# Sheet1.net
KiCad netlist of a schematic drawn in Altium Designer
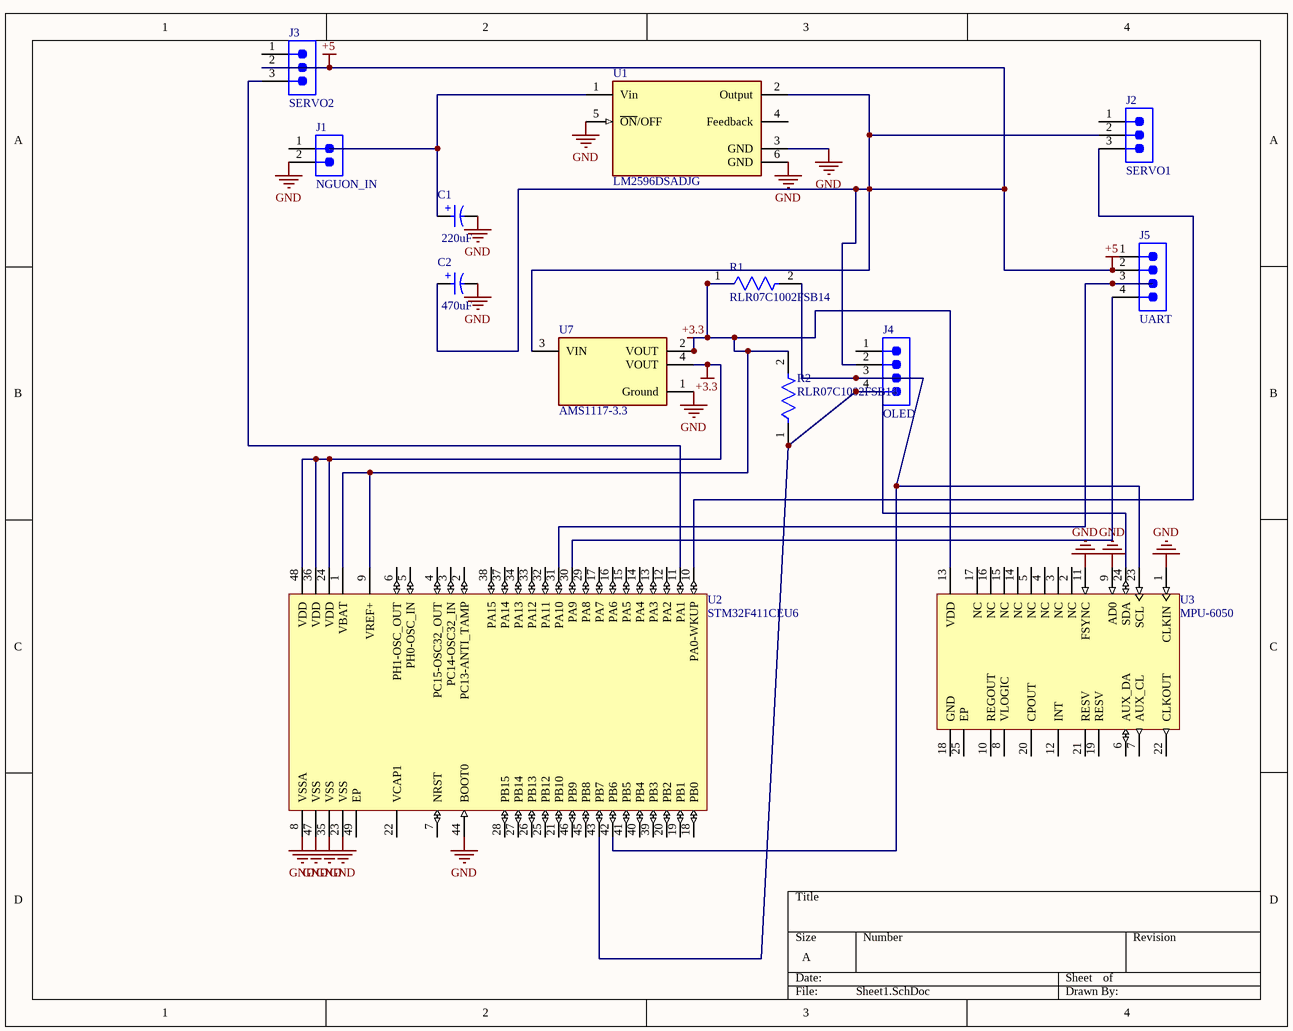
[diagram p0: Sheet1.SchDoc]

(export (version "E")
  (design (tool "Eeschema 10.0.6"))
  (components
    (comp (ref "C1")
      (value "220uF")
      (footprint "WCAP-PTHR_D8H11.5")
      (description "WCAP-PTHR Aluminum Polymer Capacitors")
      (fields (field (name "TOLERANCE") "20%"))
      (libsource (lib "Altium Content Vault") (part "Capacitor_Polarized"))
    )
    (comp (ref "C2")
      (value "470uF")
      (footprint "WCAP-PTHR_D8H11.5")
      (description "WCAP-PTHR Aluminum Polymer Capacitors")
      (fields (field (name "TOLERANCE") "20%"))
      (libsource (lib "Altium Content Vault") (part "Capacitor_Polarized"))
    )
    (comp (ref "J1")
      (value "NGUON_IN")
      (footprint "61300211121")
      (description "THT Vertical Pin Header WR-PHD, Pitch 2.54 mm, Single Row, 2 pins")
      (libsource (lib "Altium Content Vault") (part "Header_Male_1R_02P"))
    )
    (comp (ref "J2")
      (value "SERVO1")
      (footprint "61300311121")
      (description "THT Vertical Pin Header WR-PHD, Pitch 2.54 mm, Single Row, 3 pins")
      (libsource (lib "Altium Content Vault") (part "Header_Male_1R_03P"))
    )
    (comp (ref "J3")
      (value "SERVO2")
      (footprint "61300311121")
      (description "THT Vertical Pin Header WR-PHD, Pitch 2.54 mm, Single Row, 3 pins")
      (libsource (lib "Altium Content Vault") (part "Header_Male_1R_03P"))
    )
    (comp (ref "J4")
      (value "OLED")
      (footprint "61300411121")
      (description "THT Vertical Pin Header WR-PHD, Pitch 2.54 mm, Single Row, 4 pins")
      (libsource (lib "Altium Content Vault") (part "Header_Male_1R_04P"))
    )
    (comp (ref "J5")
      (value "UART")
      (footprint "61300411121")
      (description "THT Vertical Pin Header WR-PHD, Pitch 2.54 mm, Single Row, 4 pins")
      (libsource (lib "Altium Content Vault") (part "Header_Male_1R_04P"))
    )
    (comp (ref "R1")
      (value "RLR07C1002FSB14")
      (footprint "FP-RLR07-MFG")
      (fields (field (name "TOLERANCE") "1%"))
      (libsource (lib "Altium Content Vault") (part "1029c3af85768c4190bb7ad29bc67b5"))
    )
    (comp (ref "R2")
      (value "RLR07C1002FSB14")
      (footprint "FP-RLR07-MFG")
      (fields (field (name "TOLERANCE") "1%"))
      (libsource (lib "Altium Content Vault") (part "1029c3af85768c4190bb7ad29bc67b5"))
    )
    (comp (ref "U1")
      (value "LM2596DSADJG")
      (footprint "FP-936A-02-MFG")
      (description "IC REG MULT CONFG ADJ 3A D2PAK-5")
      (fields
        (field (name "OCTOPART") "https://octopart.com/lm2596dsadjg-on+semiconductor-12437034")
        (field (name "MANUFACTURER") "ON Semiconductor")
      )
      (libsource (lib "Altium Content Vault") (part "6e009c68f80b765d55aa2e30e527964"))
    )
    (comp (ref "U2")
      (value "STM32F411CEU6")
      (footprint "STM-UFQFPN48_L")
      (libsource (lib "Altium Content Vault") (part "MC-ARM-STM32F411-UFQFPN48"))
    )
    (comp (ref "U3")
      (value "MPU-6050")
      (footprint "IS-QFN-24_V")
      (fields (field (name "MANUFACTURER") "InvenSense"))
      (libsource (lib "Altium Content Vault") (part "IS-MPU-6050-QFN-24"))
    )
    (comp (ref "U7")
      (value "AMS1117-3.3")
      (footprint "FP-AMS1117-IPC_C")
      (description "LDO Voltage Regulators 1A, 3.3V")
      (fields
        (field (name "OCTOPART") "https://octopart.com/ams1117-3.3-advanced+monolithic+systems-25899300")
        (field (name "MANUFACTURER") "Advanced Monolithic Systems")
      )
      (libsource (lib "Altium Content Vault") (part "8bdbb5f8e77002000e30dd2845d0354"))
    )
  )
  (nets
    (net (code "1") (name "+3.3") (class "Default")
      (node (ref "R1") (pin "1") (pinfunction "1_1") (pintype "passive"))
      (node (ref "R2") (pin "2") (pinfunction "2_2") (pintype "passive"))
      (node (ref "U2") (pin "1") (pinfunction "VBAT_1") (pintype "power_in"))
      (node (ref "U2") (pin "24") (pinfunction "VDD_24") (pintype "power_in"))
      (node (ref "U2") (pin "36") (pinfunction "VDD_36") (pintype "power_in"))
      (node (ref "U2") (pin "48") (pinfunction "VDD_48") (pintype "power_in"))
      (node (ref "U2") (pin "9") (pinfunction "VREF+_9") (pintype "power_in"))
      (node (ref "U3") (pin "13") (pinfunction "VDD_13") (pintype "power_in"))
      (node (ref "U7") (pin "2") (pinfunction "VOUT_2") (pintype "passive"))
      (node (ref "U7") (pin "4") (pinfunction "VOUT_4") (pintype "passive"))
    )
    (net (code "2") (name "+5") (class "Default")
      (node (ref "C2") (pin "1") (pinfunction "P_1") (pintype "passive"))
      (node (ref "J2") (pin "2") (pinfunction "2_2") (pintype "passive"))
      (node (ref "J3") (pin "2") (pinfunction "2_2") (pintype "passive"))
      (node (ref "J4") (pin "2") (pinfunction "2_2") (pintype "passive"))
      (node (ref "J5") (pin "2") (pinfunction "2_2") (pintype "passive"))
      (node (ref "U1") (pin "2") (pinfunction "Output_2") (pintype "power_in"))
      (node (ref "U7") (pin "3") (pinfunction "VIN_3") (pintype "power_in"))
    )
    (net (code "3") (name "GND") (class "Default")
      (node (ref "C1") (pin "2") (pinfunction "N_2") (pintype "passive"))
      (node (ref "C2") (pin "2") (pinfunction "N_2") (pintype "passive"))
      (node (ref "J1") (pin "2") (pinfunction "2_2") (pintype "passive"))
      (node (ref "U1") (pin "3") (pinfunction "GND_3") (pintype "power_in"))
      (node (ref "U1") (pin "5") (pinfunction "~{ON}/OFF_5") (pintype "input"))
      (node (ref "U1") (pin "6") (pinfunction "GND_6") (pintype "power_in"))
      (node (ref "U2") (pin "23") (pinfunction "VSS_23") (pintype "power_in"))
      (node (ref "U2") (pin "35") (pinfunction "VSS_35") (pintype "power_in"))
      (node (ref "U2") (pin "44") (pinfunction "BOOT0_44") (pintype "input"))
      (node (ref "U2") (pin "47") (pinfunction "VSS_47") (pintype "power_in"))
      (node (ref "U2") (pin "8") (pinfunction "VSSA_8") (pintype "power_in"))
      (node (ref "U3") (pin "1") (pinfunction "CLKIN_1") (pintype "input"))
      (node (ref "U3") (pin "11") (pinfunction "FSYNC_11") (pintype "input"))
      (node (ref "U3") (pin "9") (pinfunction "AD0_9") (pintype "input"))
      (node (ref "U7") (pin "1") (pinfunction "Ground_1") (pintype "power_in"))
    )
    (net (code "4") (name "Net-(C1-P)") (class "Default")
      (node (ref "C1") (pin "1") (pinfunction "P_1") (pintype "passive"))
      (node (ref "U1") (pin "1") (pinfunction "Vin_1") (pintype "power_in"))
    )
    (net (code "5") (name "Net-(U2-PA0-WKUP)") (class "Default")
      (node (ref "J2") (pin "3") (pinfunction "3_3") (pintype "passive"))
      (node (ref "U2") (pin "10") (pinfunction "PA0-WKUP_10") (pintype "bidirectional"))
    )
    (net (code "6") (name "Net-(U2-PA1)") (class "Default")
      (node (ref "J3") (pin "3") (pinfunction "3_3") (pintype "passive"))
      (node (ref "U2") (pin "11") (pinfunction "PA1_11") (pintype "bidirectional"))
    )
    (net (code "7") (name "Net-(U2-PA9)") (class "Default")
      (node (ref "J5") (pin "4") (pinfunction "4_4") (pintype "passive"))
      (node (ref "U2") (pin "30") (pinfunction "PA9_30") (pintype "bidirectional"))
    )
    (net (code "8") (name "Net-(U2-PA10)") (class "Default")
      (node (ref "J5") (pin "3") (pinfunction "3_3") (pintype "passive"))
      (node (ref "U2") (pin "31") (pinfunction "PA10_31") (pintype "bidirectional"))
    )
    (net (code "9") (name "Net-(U2-PB6)") (class "Default")
      (node (ref "J4") (pin "3") (pinfunction "3_3") (pintype "passive"))
      (node (ref "R1") (pin "2") (pinfunction "2_2") (pintype "passive"))
      (node (ref "U2") (pin "42") (pinfunction "PB6_42") (pintype "bidirectional"))
      (node (ref "U3") (pin "23") (pinfunction "SCL_23") (pintype "input"))
    )
    (net (code "10") (name "Net-(U2-PB7)") (class "Default")
      (node (ref "J4") (pin "4") (pinfunction "4_4") (pintype "passive"))
      (node (ref "R2") (pin "1") (pinfunction "1_1") (pintype "passive"))
      (node (ref "U2") (pin "43") (pinfunction "PB7_43") (pintype "bidirectional"))
      (node (ref "U3") (pin "24") (pinfunction "SDA_24") (pintype "bidirectional"))
    )
    (net (code "11") (name "unconnected-(J1-Pad1)") (class "Default")
      (node (ref "J1") (pin "1") (pinfunction "1_1") (pintype "passive"))
    )
    (net (code "12") (name "unconnected-(J2-Pad1)") (class "Default")
      (node (ref "J2") (pin "1") (pinfunction "1_1") (pintype "passive"))
    )
    (net (code "13") (name "unconnected-(J3-Pad1)") (class "Default")
      (node (ref "J3") (pin "1") (pinfunction "1_1") (pintype "passive"))
    )
    (net (code "14") (name "unconnected-(J4-Pad1)") (class "Default")
      (node (ref "J4") (pin "1") (pinfunction "1_1") (pintype "passive"))
    )
    (net (code "15") (name "unconnected-(J5-Pad1)") (class "Default")
      (node (ref "J5") (pin "1") (pinfunction "1_1") (pintype "passive"))
    )
    (net (code "16") (name "unconnected-(U1-Feedback-Pad4)") (class "Default")
      (node (ref "U1") (pin "4") (pinfunction "Feedback_4") (pintype "passive"))
    )
    (net (code "17") (name "unconnected-(U2-EP-Pad49)") (class "Default")
      (node (ref "U2") (pin "49") (pinfunction "EP_49") (pintype "power_in"))
    )
    (net (code "18") (name "unconnected-(U2-NRST-Pad7)") (class "Default")
      (node (ref "U2") (pin "7") (pinfunction "NRST_7") (pintype "bidirectional"))
    )
    (net (code "19") (name "unconnected-(U2-PA2-Pad12)") (class "Default")
      (node (ref "U2") (pin "12") (pinfunction "PA2_12") (pintype "bidirectional"))
    )
    (net (code "20") (name "unconnected-(U2-PA3-Pad13)") (class "Default")
      (node (ref "U2") (pin "13") (pinfunction "PA3_13") (pintype "bidirectional"))
    )
    (net (code "21") (name "unconnected-(U2-PA4-Pad14)") (class "Default")
      (node (ref "U2") (pin "14") (pinfunction "PA4_14") (pintype "bidirectional"))
    )
    (net (code "22") (name "unconnected-(U2-PA5-Pad15)") (class "Default")
      (node (ref "U2") (pin "15") (pinfunction "PA5_15") (pintype "bidirectional"))
    )
    (net (code "23") (name "unconnected-(U2-PA6-Pad16)") (class "Default")
      (node (ref "U2") (pin "16") (pinfunction "PA6_16") (pintype "bidirectional"))
    )
    (net (code "24") (name "unconnected-(U2-PA7-Pad17)") (class "Default")
      (node (ref "U2") (pin "17") (pinfunction "PA7_17") (pintype "bidirectional"))
    )
    (net (code "25") (name "unconnected-(U2-PA8-Pad29)") (class "Default")
      (node (ref "U2") (pin "29") (pinfunction "PA8_29") (pintype "bidirectional"))
    )
    (net (code "26") (name "unconnected-(U2-PA11-Pad32)") (class "Default")
      (node (ref "U2") (pin "32") (pinfunction "PA11_32") (pintype "bidirectional"))
    )
    (net (code "27") (name "unconnected-(U2-PA12-Pad33)") (class "Default")
      (node (ref "U2") (pin "33") (pinfunction "PA12_33") (pintype "bidirectional"))
    )
    (net (code "28") (name "unconnected-(U2-PA13-Pad34)") (class "Default")
      (node (ref "U2") (pin "34") (pinfunction "PA13_34") (pintype "bidirectional"))
    )
    (net (code "29") (name "unconnected-(U2-PA14-Pad37)") (class "Default")
      (node (ref "U2") (pin "37") (pinfunction "PA14_37") (pintype "bidirectional"))
    )
    (net (code "30") (name "unconnected-(U2-PA15-Pad38)") (class "Default")
      (node (ref "U2") (pin "38") (pinfunction "PA15_38") (pintype "bidirectional"))
    )
    (net (code "31") (name "unconnected-(U2-PB0-Pad18)") (class "Default")
      (node (ref "U2") (pin "18") (pinfunction "PB0_18") (pintype "bidirectional"))
    )
    (net (code "32") (name "unconnected-(U2-PB1-Pad19)") (class "Default")
      (node (ref "U2") (pin "19") (pinfunction "PB1_19") (pintype "bidirectional"))
    )
    (net (code "33") (name "unconnected-(U2-PB2-Pad20)") (class "Default")
      (node (ref "U2") (pin "20") (pinfunction "PB2_20") (pintype "bidirectional"))
    )
    (net (code "34") (name "unconnected-(U2-PB3-Pad39)") (class "Default")
      (node (ref "U2") (pin "39") (pinfunction "PB3_39") (pintype "bidirectional"))
    )
    (net (code "35") (name "unconnected-(U2-PB4-Pad40)") (class "Default")
      (node (ref "U2") (pin "40") (pinfunction "PB4_40") (pintype "bidirectional"))
    )
    (net (code "36") (name "unconnected-(U2-PB5-Pad41)") (class "Default")
      (node (ref "U2") (pin "41") (pinfunction "PB5_41") (pintype "bidirectional"))
    )
    (net (code "37") (name "unconnected-(U2-PB8-Pad45)") (class "Default")
      (node (ref "U2") (pin "45") (pinfunction "PB8_45") (pintype "bidirectional"))
    )
    (net (code "38") (name "unconnected-(U2-PB9-Pad46)") (class "Default")
      (node (ref "U2") (pin "46") (pinfunction "PB9_46") (pintype "bidirectional"))
    )
    (net (code "39") (name "unconnected-(U2-PB10-Pad21)") (class "Default")
      (node (ref "U2") (pin "21") (pinfunction "PB10_21") (pintype "bidirectional"))
    )
    (net (code "40") (name "unconnected-(U2-PB12-Pad25)") (class "Default")
      (node (ref "U2") (pin "25") (pinfunction "PB12_25") (pintype "bidirectional"))
    )
    (net (code "41") (name "unconnected-(U2-PB13-Pad26)") (class "Default")
      (node (ref "U2") (pin "26") (pinfunction "PB13_26") (pintype "bidirectional"))
    )
    (net (code "42") (name "unconnected-(U2-PB14-Pad27)") (class "Default")
      (node (ref "U2") (pin "27") (pinfunction "PB14_27") (pintype "bidirectional"))
    )
    (net (code "43") (name "unconnected-(U2-PB15-Pad28)") (class "Default")
      (node (ref "U2") (pin "28") (pinfunction "PB15_28") (pintype "bidirectional"))
    )
    (net (code "44") (name "unconnected-(U2-PC13-ANTI_TAMP-Pad2)") (class "Default")
      (node (ref "U2") (pin "2") (pinfunction "PC13-ANTI_TAMP_2") (pintype "bidirectional"))
    )
    (net (code "45") (name "unconnected-(U2-PC14-OSC32_IN-Pad3)") (class "Default")
      (node (ref "U2") (pin "3") (pinfunction "PC14-OSC32_IN_3") (pintype "bidirectional"))
    )
    (net (code "46") (name "unconnected-(U2-PC15-OSC32_OUT-Pad4)") (class "Default")
      (node (ref "U2") (pin "4") (pinfunction "PC15-OSC32_OUT_4") (pintype "bidirectional"))
    )
    (net (code "47") (name "unconnected-(U2-PH0-OSC_IN-Pad5)") (class "Default")
      (node (ref "U2") (pin "5") (pinfunction "PH0-OSC_IN_5") (pintype "bidirectional"))
    )
    (net (code "48") (name "unconnected-(U2-PH1-OSC_OUT-Pad6)") (class "Default")
      (node (ref "U2") (pin "6") (pinfunction "PH1-OSC_OUT_6") (pintype "bidirectional"))
    )
    (net (code "49") (name "unconnected-(U2-VCAP1-Pad22)") (class "Default")
      (node (ref "U2") (pin "22") (pinfunction "VCAP1_22") (pintype "passive"))
    )
    (net (code "50") (name "unconnected-(U3-AUX_CL-Pad7)") (class "Default")
      (node (ref "U3") (pin "7") (pinfunction "AUX_CL_7") (pintype "output"))
    )
    (net (code "51") (name "unconnected-(U3-AUX_DA-Pad6)") (class "Default")
      (node (ref "U3") (pin "6") (pinfunction "AUX_DA_6") (pintype "bidirectional"))
    )
    (net (code "52") (name "unconnected-(U3-CLKOUT-Pad22)") (class "Default")
      (node (ref "U3") (pin "22") (pinfunction "CLKOUT_22") (pintype "output"))
    )
    (net (code "53") (name "unconnected-(U3-CPOUT-Pad20)") (class "Default")
      (node (ref "U3") (pin "20") (pinfunction "CPOUT_20") (pintype "passive"))
    )
    (net (code "54") (name "unconnected-(U3-EP-Pad25)") (class "Default")
      (node (ref "U3") (pin "25") (pinfunction "EP_25") (pintype "power_in"))
    )
    (net (code "55") (name "unconnected-(U3-GND-Pad18)") (class "Default")
      (node (ref "U3") (pin "18") (pinfunction "GND_18") (pintype "power_in"))
    )
    (net (code "56") (name "unconnected-(U3-INT-Pad12)") (class "Default")
      (node (ref "U3") (pin "12") (pinfunction "INT_12") (pintype "open_collector"))
    )
    (net (code "57") (name "unconnected-(U3-NC-Pad2)") (class "Default")
      (node (ref "U3") (pin "2") (pinfunction "NC_2") (pintype "passive"))
    )
    (net (code "58") (name "unconnected-(U3-NC-Pad3)") (class "Default")
      (node (ref "U3") (pin "3") (pinfunction "NC_3") (pintype "passive"))
    )
    (net (code "59") (name "unconnected-(U3-NC-Pad4)") (class "Default")
      (node (ref "U3") (pin "4") (pinfunction "NC_4") (pintype "passive"))
    )
    (net (code "60") (name "unconnected-(U3-NC-Pad5)") (class "Default")
      (node (ref "U3") (pin "5") (pinfunction "NC_5") (pintype "passive"))
    )
    (net (code "61") (name "unconnected-(U3-NC-Pad14)") (class "Default")
      (node (ref "U3") (pin "14") (pinfunction "NC_14") (pintype "passive"))
    )
    (net (code "62") (name "unconnected-(U3-NC-Pad15)") (class "Default")
      (node (ref "U3") (pin "15") (pinfunction "NC_15") (pintype "passive"))
    )
    (net (code "63") (name "unconnected-(U3-NC-Pad16)") (class "Default")
      (node (ref "U3") (pin "16") (pinfunction "NC_16") (pintype "passive"))
    )
    (net (code "64") (name "unconnected-(U3-NC-Pad17)") (class "Default")
      (node (ref "U3") (pin "17") (pinfunction "NC_17") (pintype "passive"))
    )
    (net (code "65") (name "unconnected-(U3-REGOUT-Pad10)") (class "Default")
      (node (ref "U3") (pin "10") (pinfunction "REGOUT_10") (pintype "passive"))
    )
    (net (code "66") (name "unconnected-(U3-RESV-Pad19)") (class "Default")
      (node (ref "U3") (pin "19") (pinfunction "RESV_19") (pintype "passive"))
    )
    (net (code "67") (name "unconnected-(U3-RESV-Pad21)") (class "Default")
      (node (ref "U3") (pin "21") (pinfunction "RESV_21") (pintype "passive"))
    )
    (net (code "68") (name "unconnected-(U3-VLOGIC-Pad8)") (class "Default")
      (node (ref "U3") (pin "8") (pinfunction "VLOGIC_8") (pintype "power_in"))
    )
  )
)
